# jangeles.net
KiCad netlist of a schematic drawn in EAGLE
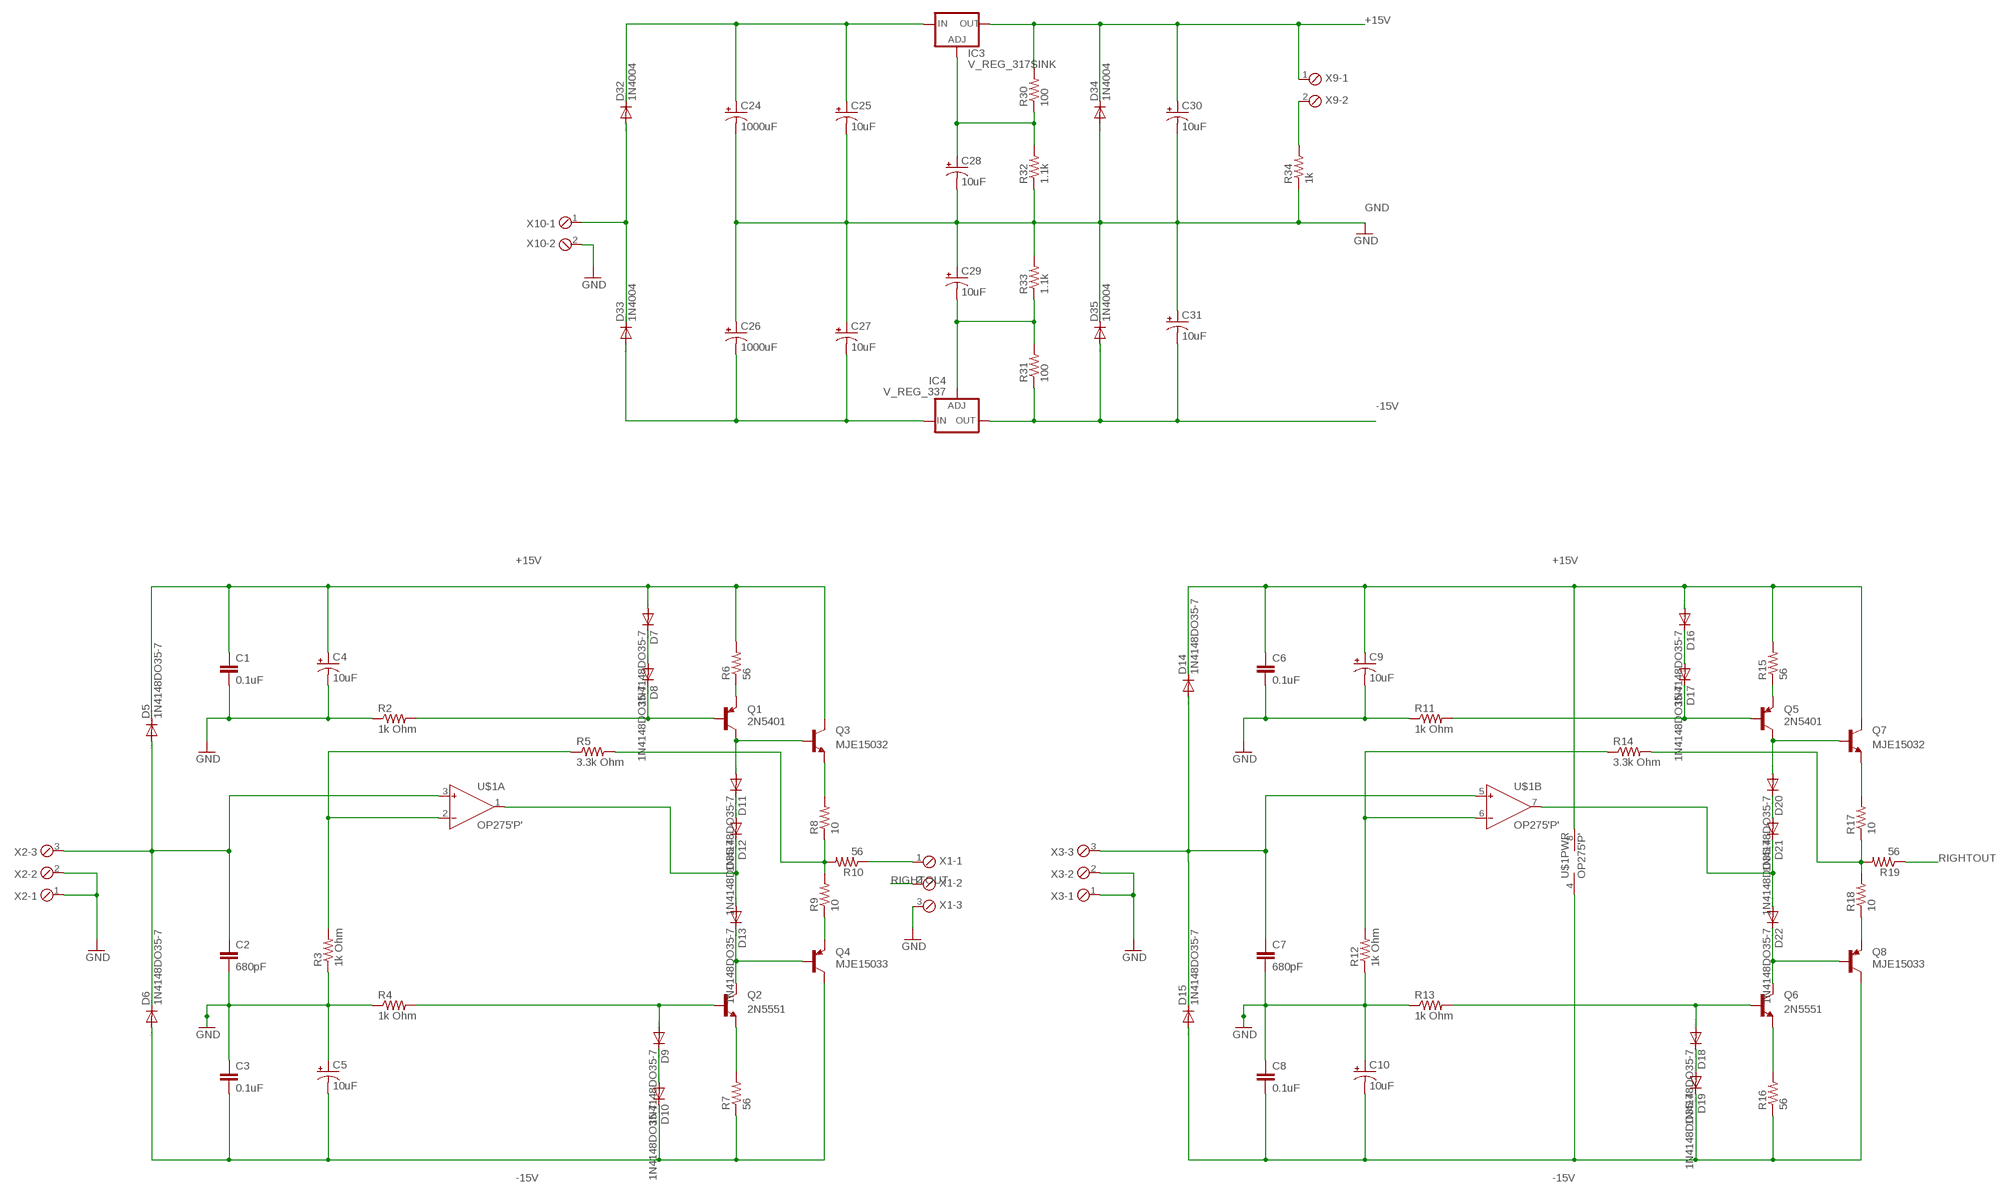
[diagram p0: schematic, sheet 1]

(export (version "E")
  (design (tool "Eeschema 10.0.6"))
  (components
    (comp (ref "C1")
      (value "0.1uF")
      (footprint "eagle-import:C025-024X044")
      (libsource (lib "eagle-import") (part "C-EU025-024X044"))
    )
    (comp (ref "C2")
      (value "680pF")
      (footprint "eagle-import:C025-024X044")
      (libsource (lib "eagle-import") (part "C-EU025-024X044"))
    )
    (comp (ref "C3")
      (value "0.1uF")
      (footprint "eagle-import:C025-024X044")
      (libsource (lib "eagle-import") (part "C-EU025-024X044"))
    )
    (comp (ref "C4")
      (value "10uF")
      (footprint "eagle-import:E2-5")
      (libsource (lib "eagle-import") (part "CPOL-USE2-5"))
    )
    (comp (ref "C5")
      (value "10uF")
      (footprint "eagle-import:E2-5")
      (libsource (lib "eagle-import") (part "CPOL-USE2-5"))
    )
    (comp (ref "C6")
      (value "0.1uF")
      (footprint "eagle-import:C025-024X044")
      (libsource (lib "eagle-import") (part "C-EU025-024X044"))
    )
    (comp (ref "C7")
      (value "680pF")
      (footprint "eagle-import:C025-024X044")
      (libsource (lib "eagle-import") (part "C-EU025-024X044"))
    )
    (comp (ref "C8")
      (value "0.1uF")
      (footprint "eagle-import:C025-024X044")
      (libsource (lib "eagle-import") (part "C-EU025-024X044"))
    )
    (comp (ref "C9")
      (value "10uF")
      (footprint "eagle-import:E2-5")
      (libsource (lib "eagle-import") (part "CPOL-USE2-5"))
    )
    (comp (ref "C10")
      (value "10uF")
      (footprint "eagle-import:E2-5")
      (libsource (lib "eagle-import") (part "CPOL-USE2-5"))
    )
    (comp (ref "C24")
      (value "1000uF")
      (footprint "eagle-import:E5-10,5")
      (libsource (lib "eagle-import") (part "CPOL-USE5-10.5"))
    )
    (comp (ref "C25")
      (value "10uF")
      (footprint "eagle-import:E2-5")
      (libsource (lib "eagle-import") (part "CPOL-USE2-5"))
    )
    (comp (ref "C26")
      (value "1000uF")
      (footprint "eagle-import:E5-10,5")
      (libsource (lib "eagle-import") (part "CPOL-USE5-10.5"))
    )
    (comp (ref "C27")
      (value "10uF")
      (footprint "eagle-import:E2-5")
      (libsource (lib "eagle-import") (part "CPOL-USE2-5"))
    )
    (comp (ref "C28")
      (value "10uF")
      (footprint "eagle-import:E2-5")
      (libsource (lib "eagle-import") (part "CPOL-USE2-5"))
    )
    (comp (ref "C29")
      (value "10uF")
      (footprint "eagle-import:E2-5")
      (libsource (lib "eagle-import") (part "CPOL-USE2-5"))
    )
    (comp (ref "C30")
      (value "10uF")
      (footprint "eagle-import:E2-5")
      (libsource (lib "eagle-import") (part "CPOL-USE2-5"))
    )
    (comp (ref "C31")
      (value "10uF")
      (footprint "eagle-import:E2-5")
      (libsource (lib "eagle-import") (part "CPOL-USE2-5"))
    )
    (comp (ref "D5")
      (value "1N4148DO35-7")
      (footprint "eagle-import:DO35-7")
      (libsource (lib "eagle-import") (part "1N4148DO35-7"))
    )
    (comp (ref "D6")
      (value "1N4148DO35-7")
      (footprint "eagle-import:DO35-7")
      (libsource (lib "eagle-import") (part "1N4148DO35-7"))
    )
    (comp (ref "D7")
      (value "1N4148DO35-7")
      (footprint "eagle-import:DO35-7")
      (libsource (lib "eagle-import") (part "1N4148DO35-7"))
    )
    (comp (ref "D8")
      (value "1N4148DO35-7")
      (footprint "eagle-import:DO35-7")
      (libsource (lib "eagle-import") (part "1N4148DO35-7"))
    )
    (comp (ref "D9")
      (value "1N4148DO35-7")
      (footprint "eagle-import:DO35-7")
      (libsource (lib "eagle-import") (part "1N4148DO35-7"))
    )
    (comp (ref "D10")
      (value "1N4148DO35-7")
      (footprint "eagle-import:DO35-7")
      (libsource (lib "eagle-import") (part "1N4148DO35-7"))
    )
    (comp (ref "D11")
      (value "1N4148DO35-7")
      (footprint "eagle-import:DO35-7")
      (libsource (lib "eagle-import") (part "1N4148DO35-7"))
    )
    (comp (ref "D12")
      (value "1N4148DO35-7")
      (footprint "eagle-import:DO35-7")
      (libsource (lib "eagle-import") (part "1N4148DO35-7"))
    )
    (comp (ref "D13")
      (value "1N4148DO35-7")
      (footprint "eagle-import:DO35-7")
      (libsource (lib "eagle-import") (part "1N4148DO35-7"))
    )
    (comp (ref "D14")
      (value "1N4148DO35-7")
      (footprint "eagle-import:DO35-7")
      (libsource (lib "eagle-import") (part "1N4148DO35-7"))
    )
    (comp (ref "D15")
      (value "1N4148DO35-7")
      (footprint "eagle-import:DO35-7")
      (libsource (lib "eagle-import") (part "1N4148DO35-7"))
    )
    (comp (ref "D16")
      (value "1N4148DO35-7")
      (footprint "eagle-import:DO35-7")
      (libsource (lib "eagle-import") (part "1N4148DO35-7"))
    )
    (comp (ref "D17")
      (value "1N4148DO35-7")
      (footprint "eagle-import:DO35-7")
      (libsource (lib "eagle-import") (part "1N4148DO35-7"))
    )
    (comp (ref "D18")
      (value "1N4148DO35-7")
      (footprint "eagle-import:DO35-7")
      (libsource (lib "eagle-import") (part "1N4148DO35-7"))
    )
    (comp (ref "D19")
      (value "1N4148DO35-7")
      (footprint "eagle-import:DO35-7")
      (libsource (lib "eagle-import") (part "1N4148DO35-7"))
    )
    (comp (ref "D20")
      (value "1N4148DO35-7")
      (footprint "eagle-import:DO35-7")
      (libsource (lib "eagle-import") (part "1N4148DO35-7"))
    )
    (comp (ref "D21")
      (value "1N4148DO35-7")
      (footprint "eagle-import:DO35-7")
      (libsource (lib "eagle-import") (part "1N4148DO35-7"))
    )
    (comp (ref "D22")
      (value "1N4148DO35-7")
      (footprint "eagle-import:DO35-7")
      (libsource (lib "eagle-import") (part "1N4148DO35-7"))
    )
    (comp (ref "D32")
      (value "1N4004")
      (footprint "eagle-import:DO41-10")
      (libsource (lib "eagle-import") (part "1N4004"))
    )
    (comp (ref "D33")
      (value "1N4004")
      (footprint "eagle-import:DO41-10")
      (libsource (lib "eagle-import") (part "1N4004"))
    )
    (comp (ref "D34")
      (value "1N4004")
      (footprint "eagle-import:DO41-10")
      (libsource (lib "eagle-import") (part "1N4004"))
    )
    (comp (ref "D35")
      (value "1N4004")
      (footprint "eagle-import:DO41-10")
      (libsource (lib "eagle-import") (part "1N4004"))
    )
    (comp (ref "IC3")
      (value "V_REG_317SINK")
      (footprint "eagle-import:TO220-ADJ")
      (libsource (lib "eagle-import") (part "V_REG_317SINK"))
    )
    (comp (ref "IC4")
      (value "V_REG_337")
      (footprint "eagle-import:TO220-ADJ-NEG")
      (libsource (lib "eagle-import") (part "V_REG_337"))
    )
    (comp (ref "Q1")
      (value "2N5401")
      (footprint "eagle-import:2N5401")
      (libsource (lib "eagle-import") (part "2N5401"))
    )
    (comp (ref "Q2")
      (value "2N5551")
      (footprint "eagle-import:2N5551")
      (libsource (lib "eagle-import") (part "2N5551"))
    )
    (comp (ref "Q3")
      (value "MJE15032")
      (footprint "eagle-import:TO220V")
      (libsource (lib "eagle-import") (part "MJE15032"))
    )
    (comp (ref "Q4")
      (value "MJE15033")
      (footprint "eagle-import:TO220V")
      (libsource (lib "eagle-import") (part "MJE15033"))
    )
    (comp (ref "Q5")
      (value "2N5401")
      (footprint "eagle-import:2N5401")
      (libsource (lib "eagle-import") (part "2N5401"))
    )
    (comp (ref "Q6")
      (value "2N5551")
      (footprint "eagle-import:2N5551")
      (libsource (lib "eagle-import") (part "2N5551"))
    )
    (comp (ref "Q7")
      (value "MJE15032")
      (footprint "eagle-import:TO220V")
      (libsource (lib "eagle-import") (part "MJE15032"))
    )
    (comp (ref "Q8")
      (value "MJE15033")
      (footprint "eagle-import:TO220V")
      (libsource (lib "eagle-import") (part "MJE15033"))
    )
    (comp (ref "R2")
      (value "1k Ohm")
      (footprint "eagle-import:0204_5")
      (libsource (lib "eagle-import") (part "R-US_0204/5"))
    )
    (comp (ref "R3")
      (value "1k Ohm")
      (footprint "eagle-import:0204_5")
      (libsource (lib "eagle-import") (part "R-US_0204/5"))
    )
    (comp (ref "R4")
      (value "1k Ohm")
      (footprint "eagle-import:0204_5")
      (libsource (lib "eagle-import") (part "R-US_0204/5"))
    )
    (comp (ref "R5")
      (value "3.3k Ohm")
      (footprint "eagle-import:0204_5")
      (libsource (lib "eagle-import") (part "R-US_0204/5"))
    )
    (comp (ref "R6")
      (value "56")
      (footprint "eagle-import:0204_5")
      (libsource (lib "eagle-import") (part "R-US_0204/5"))
    )
    (comp (ref "R7")
      (value "56")
      (footprint "eagle-import:0204_5")
      (libsource (lib "eagle-import") (part "R-US_0204/5"))
    )
    (comp (ref "R8")
      (value "10")
      (footprint "eagle-import:0204_5")
      (libsource (lib "eagle-import") (part "R-US_0204/5"))
    )
    (comp (ref "R9")
      (value "10")
      (footprint "eagle-import:0204_5")
      (libsource (lib "eagle-import") (part "R-US_0204/5"))
    )
    (comp (ref "R10")
      (value "56")
      (footprint "eagle-import:0204_5")
      (libsource (lib "eagle-import") (part "R-US_0204/5"))
    )
    (comp (ref "R11")
      (value "1k Ohm")
      (footprint "eagle-import:0204_5")
      (libsource (lib "eagle-import") (part "R-US_0204/5"))
    )
    (comp (ref "R12")
      (value "1k Ohm")
      (footprint "eagle-import:0204_5")
      (libsource (lib "eagle-import") (part "R-US_0204/5"))
    )
    (comp (ref "R13")
      (value "1k Ohm")
      (footprint "eagle-import:0204_5")
      (libsource (lib "eagle-import") (part "R-US_0204/5"))
    )
    (comp (ref "R14")
      (value "3.3k Ohm")
      (footprint "eagle-import:0204_5")
      (libsource (lib "eagle-import") (part "R-US_0204/5"))
    )
    (comp (ref "R15")
      (value "56")
      (footprint "eagle-import:0204_5")
      (libsource (lib "eagle-import") (part "R-US_0204/5"))
    )
    (comp (ref "R16")
      (value "56")
      (footprint "eagle-import:0204_5")
      (libsource (lib "eagle-import") (part "R-US_0204/5"))
    )
    (comp (ref "R17")
      (value "10")
      (footprint "eagle-import:0204_5")
      (libsource (lib "eagle-import") (part "R-US_0204/5"))
    )
    (comp (ref "R18")
      (value "10")
      (footprint "eagle-import:0204_5")
      (libsource (lib "eagle-import") (part "R-US_0204/5"))
    )
    (comp (ref "R19")
      (value "56")
      (footprint "eagle-import:0204_5")
      (libsource (lib "eagle-import") (part "R-US_0204/5"))
    )
    (comp (ref "R30")
      (value "100")
      (footprint "eagle-import:0309_10")
      (libsource (lib "eagle-import") (part "R-US_0309/10"))
    )
    (comp (ref "R31")
      (value "100")
      (footprint "eagle-import:0309_10")
      (libsource (lib "eagle-import") (part "R-US_0309/10"))
    )
    (comp (ref "R32")
      (value "1.1k")
      (footprint "eagle-import:0204_5")
      (libsource (lib "eagle-import") (part "R-US_0204/5"))
    )
    (comp (ref "R33")
      (value "1.1k")
      (footprint "eagle-import:0204_5")
      (libsource (lib "eagle-import") (part "R-US_0204/5"))
    )
    (comp (ref "R34")
      (value "1k")
      (footprint "eagle-import:0204_5")
      (libsource (lib "eagle-import") (part "R-US_0204/5"))
    )
    (comp (ref "U$1")
      (value "OP275'P'")
      (footprint "eagle-import:DIL08")
      (libsource (lib "eagle-import") (part "OP275'P'"))
    )
    (comp (ref "X1")
      (value "MPT3")
      (footprint "eagle-import:3POL254")
      (libsource (lib "eagle-import") (part "MPT3"))
    )
    (comp (ref "X2")
      (value "MPT3")
      (footprint "eagle-import:3POL254")
      (libsource (lib "eagle-import") (part "MPT3"))
    )
    (comp (ref "X3")
      (value "MPT3")
      (footprint "eagle-import:3POL254")
      (libsource (lib "eagle-import") (part "MPT3"))
    )
    (comp (ref "X9")
      (value "MPT2")
      (footprint "eagle-import:2POL254")
      (libsource (lib "eagle-import") (part "MPT2"))
    )
    (comp (ref "X10")
      (value "MPT2")
      (footprint "eagle-import:2POL254")
      (libsource (lib "eagle-import") (part "MPT2"))
    )
  )
  (nets
    (net (code "1") (name "/+15V") (class "Default")
      (node (ref "C1") (pin "1") (pinfunction "1_1") (pintype "passive"))
      (node (ref "C30") (pin "+") (pinfunction "+_+") (pintype "passive"))
      (node (ref "C4") (pin "+") (pinfunction "+_+") (pintype "passive"))
      (node (ref "C6") (pin "1") (pinfunction "1_1") (pintype "passive"))
      (node (ref "C9") (pin "+") (pinfunction "+_+") (pintype "passive"))
      (node (ref "D14") (pin "C") (pinfunction "C_C") (pintype "passive"))
      (node (ref "D16") (pin "A") (pinfunction "A_A") (pintype "passive"))
      (node (ref "D34") (pin "C") (pinfunction "C_C") (pintype "passive"))
      (node (ref "D5") (pin "C") (pinfunction "C_C") (pintype "passive"))
      (node (ref "D7") (pin "A") (pinfunction "A_A") (pintype "passive"))
      (node (ref "IC3") (pin "OUT") (pinfunction "OUT_OUT") (pintype "output"))
      (node (ref "Q3") (pin "2") (pinfunction "C_2") (pintype "passive"))
      (node (ref "Q7") (pin "2") (pinfunction "C_2") (pintype "passive"))
      (node (ref "R15") (pin "2") (pinfunction "2_2") (pintype "passive"))
      (node (ref "R30") (pin "2") (pinfunction "2_2") (pintype "passive"))
      (node (ref "R6") (pin "2") (pinfunction "2_2") (pintype "passive"))
      (node (ref "U$1") (pin "8") (pinfunction "V+_8") (pintype "power_in"))
      (node (ref "X9") (pin "1") (pinfunction "1_1") (pintype "passive"))
    )
    (net (code "2") (name "/-15V") (class "Default")
      (node (ref "C10") (pin "-") (pinfunction "-_-") (pintype "passive"))
      (node (ref "C3") (pin "2") (pinfunction "2_2") (pintype "passive"))
      (node (ref "C31") (pin "-") (pinfunction "-_-") (pintype "passive"))
      (node (ref "C5") (pin "-") (pinfunction "-_-") (pintype "passive"))
      (node (ref "C8") (pin "2") (pinfunction "2_2") (pintype "passive"))
      (node (ref "D10") (pin "C") (pinfunction "C_C") (pintype "passive"))
      (node (ref "D15") (pin "A") (pinfunction "A_A") (pintype "passive"))
      (node (ref "D19") (pin "C") (pinfunction "C_C") (pintype "passive"))
      (node (ref "D35") (pin "A") (pinfunction "A_A") (pintype "passive"))
      (node (ref "D6") (pin "A") (pinfunction "A_A") (pintype "passive"))
      (node (ref "IC4") (pin "OUT") (pinfunction "OUT_OUT") (pintype "output"))
      (node (ref "Q4") (pin "2") (pinfunction "C_2") (pintype "passive"))
      (node (ref "Q8") (pin "2") (pinfunction "C_2") (pintype "passive"))
      (node (ref "R16") (pin "1") (pinfunction "1_1") (pintype "passive"))
      (node (ref "R31") (pin "1") (pinfunction "1_1") (pintype "passive"))
      (node (ref "R7") (pin "1") (pinfunction "1_1") (pintype "passive"))
      (node (ref "U$1") (pin "4") (pinfunction "V-_4") (pintype "power_in"))
    )
    (net (code "3") (name "/RIGHTOUT") (class "Default")
      (node (ref "R19") (pin "1") (pinfunction "1_1") (pintype "passive"))
      (node (ref "X1") (pin "2") (pinfunction "1_2") (pintype "passive"))
    )
    (net (code "4") (name "GND") (class "Default")
      (node (ref "C1") (pin "2") (pinfunction "2_2") (pintype "passive"))
      (node (ref "C10") (pin "+") (pinfunction "+_+") (pintype "passive"))
      (node (ref "C2") (pin "2") (pinfunction "2_2") (pintype "passive"))
      (node (ref "C24") (pin "-") (pinfunction "-_-") (pintype "passive"))
      (node (ref "C25") (pin "-") (pinfunction "-_-") (pintype "passive"))
      (node (ref "C26") (pin "+") (pinfunction "+_+") (pintype "passive"))
      (node (ref "C27") (pin "+") (pinfunction "+_+") (pintype "passive"))
      (node (ref "C28") (pin "-") (pinfunction "-_-") (pintype "passive"))
      (node (ref "C29") (pin "+") (pinfunction "+_+") (pintype "passive"))
      (node (ref "C3") (pin "1") (pinfunction "1_1") (pintype "passive"))
      (node (ref "C30") (pin "-") (pinfunction "-_-") (pintype "passive"))
      (node (ref "C31") (pin "+") (pinfunction "+_+") (pintype "passive"))
      (node (ref "C4") (pin "-") (pinfunction "-_-") (pintype "passive"))
      (node (ref "C5") (pin "+") (pinfunction "+_+") (pintype "passive"))
      (node (ref "C6") (pin "2") (pinfunction "2_2") (pintype "passive"))
      (node (ref "C7") (pin "2") (pinfunction "2_2") (pintype "passive"))
      (node (ref "C8") (pin "1") (pinfunction "1_1") (pintype "passive"))
      (node (ref "C9") (pin "-") (pinfunction "-_-") (pintype "passive"))
      (node (ref "D34") (pin "A") (pinfunction "A_A") (pintype "passive"))
      (node (ref "D35") (pin "C") (pinfunction "C_C") (pintype "passive"))
      (node (ref "R11") (pin "1") (pinfunction "1_1") (pintype "passive"))
      (node (ref "R12") (pin "1") (pinfunction "1_1") (pintype "passive"))
      (node (ref "R13") (pin "1") (pinfunction "1_1") (pintype "passive"))
      (node (ref "R2") (pin "1") (pinfunction "1_1") (pintype "passive"))
      (node (ref "R3") (pin "1") (pinfunction "1_1") (pintype "passive"))
      (node (ref "R32") (pin "1") (pinfunction "1_1") (pintype "passive"))
      (node (ref "R33") (pin "2") (pinfunction "2_2") (pintype "passive"))
      (node (ref "R34") (pin "1") (pinfunction "1_1") (pintype "passive"))
      (node (ref "R4") (pin "1") (pinfunction "1_1") (pintype "passive"))
      (node (ref "X1") (pin "3") (pinfunction "1_3") (pintype "passive"))
      (node (ref "X10") (pin "2") (pinfunction "1_2") (pintype "passive"))
      (node (ref "X2") (pin "1") (pinfunction "1_1") (pintype "passive"))
      (node (ref "X2") (pin "2") (pinfunction "1_2") (pintype "passive"))
      (node (ref "X3") (pin "1") (pinfunction "1_1") (pintype "passive"))
      (node (ref "X3") (pin "2") (pinfunction "1_2") (pintype "passive"))
    )
    (net (code "5") (name "Net-(C24-Pad+)") (class "Default")
      (node (ref "C24") (pin "+") (pinfunction "+_+") (pintype "passive"))
      (node (ref "C25") (pin "+") (pinfunction "+_+") (pintype "passive"))
      (node (ref "D32") (pin "C") (pinfunction "C_C") (pintype "passive"))
      (node (ref "IC3") (pin "IN") (pinfunction "IN_IN") (pintype "input"))
    )
    (net (code "6") (name "Net-(C26-Pad-)") (class "Default")
      (node (ref "C26") (pin "-") (pinfunction "-_-") (pintype "passive"))
      (node (ref "C27") (pin "-") (pinfunction "-_-") (pintype "passive"))
      (node (ref "D33") (pin "A") (pinfunction "A_A") (pintype "passive"))
      (node (ref "IC4") (pin "IN") (pinfunction "IN_IN") (pintype "input"))
    )
    (net (code "7") (name "Net-(C28-Pad+)") (class "Default")
      (node (ref "C28") (pin "+") (pinfunction "+_+") (pintype "passive"))
      (node (ref "IC3") (pin "ADJ") (pinfunction "ADJ_ADJ") (pintype "input"))
      (node (ref "R30") (pin "1") (pinfunction "1_1") (pintype "passive"))
      (node (ref "R32") (pin "2") (pinfunction "2_2") (pintype "passive"))
    )
    (net (code "8") (name "Net-(C29-Pad-)") (class "Default")
      (node (ref "C29") (pin "-") (pinfunction "-_-") (pintype "passive"))
      (node (ref "IC4") (pin "ADJ") (pinfunction "ADJ_ADJ") (pintype "input"))
      (node (ref "R31") (pin "2") (pinfunction "2_2") (pintype "passive"))
      (node (ref "R33") (pin "1") (pinfunction "1_1") (pintype "passive"))
    )
    (net (code "9") (name "Net-(D7-PadC)") (class "Default")
      (node (ref "D7") (pin "C") (pinfunction "C_C") (pintype "passive"))
      (node (ref "D8") (pin "A") (pinfunction "A_A") (pintype "passive"))
    )
    (net (code "10") (name "Net-(D8-PadC)") (class "Default")
      (node (ref "D8") (pin "C") (pinfunction "C_C") (pintype "passive"))
      (node (ref "Q1") (pin "B") (pinfunction "B_B") (pintype "passive"))
      (node (ref "R2") (pin "2") (pinfunction "2_2") (pintype "passive"))
    )
    (net (code "11") (name "Net-(D9-PadA)") (class "Default")
      (node (ref "D9") (pin "A") (pinfunction "A_A") (pintype "passive"))
      (node (ref "Q2") (pin "B") (pinfunction "B_B") (pintype "passive"))
      (node (ref "R4") (pin "2") (pinfunction "2_2") (pintype "passive"))
    )
    (net (code "12") (name "Net-(D10-PadA)") (class "Default")
      (node (ref "D10") (pin "A") (pinfunction "A_A") (pintype "passive"))
      (node (ref "D9") (pin "C") (pinfunction "C_C") (pintype "passive"))
    )
    (net (code "13") (name "Net-(D11-PadC)") (class "Default")
      (node (ref "D11") (pin "C") (pinfunction "C_C") (pintype "passive"))
      (node (ref "D12") (pin "A") (pinfunction "A_A") (pintype "passive"))
    )
    (net (code "14") (name "Net-(D16-PadC)") (class "Default")
      (node (ref "D16") (pin "C") (pinfunction "C_C") (pintype "passive"))
      (node (ref "D17") (pin "A") (pinfunction "A_A") (pintype "passive"))
    )
    (net (code "15") (name "Net-(D17-PadC)") (class "Default")
      (node (ref "D17") (pin "C") (pinfunction "C_C") (pintype "passive"))
      (node (ref "Q5") (pin "B") (pinfunction "B_B") (pintype "passive"))
      (node (ref "R11") (pin "2") (pinfunction "2_2") (pintype "passive"))
    )
    (net (code "16") (name "Net-(D18-PadA)") (class "Default")
      (node (ref "D18") (pin "A") (pinfunction "A_A") (pintype "passive"))
      (node (ref "Q6") (pin "B") (pinfunction "B_B") (pintype "passive"))
      (node (ref "R13") (pin "2") (pinfunction "2_2") (pintype "passive"))
    )
    (net (code "17") (name "Net-(D18-PadC)") (class "Default")
      (node (ref "D18") (pin "C") (pinfunction "C_C") (pintype "passive"))
      (node (ref "D19") (pin "A") (pinfunction "A_A") (pintype "passive"))
    )
    (net (code "18") (name "Net-(D20-PadC)") (class "Default")
      (node (ref "D20") (pin "C") (pinfunction "C_C") (pintype "passive"))
      (node (ref "D21") (pin "A") (pinfunction "A_A") (pintype "passive"))
    )
    (net (code "19") (name "Net-(D32-PadA)") (class "Default")
      (node (ref "D32") (pin "A") (pinfunction "A_A") (pintype "passive"))
      (node (ref "D33") (pin "C") (pinfunction "C_C") (pintype "passive"))
      (node (ref "X10") (pin "1") (pinfunction "1_1") (pintype "passive"))
    )
    (net (code "20") (name "Net-(Q1-PadE)") (class "Default")
      (node (ref "Q1") (pin "E") (pinfunction "E_E") (pintype "passive"))
      (node (ref "R6") (pin "1") (pinfunction "1_1") (pintype "passive"))
    )
    (net (code "21") (name "Net-(Q2-PadE)") (class "Default")
      (node (ref "Q2") (pin "E") (pinfunction "E_E") (pintype "passive"))
      (node (ref "R7") (pin "2") (pinfunction "2_2") (pintype "passive"))
    )
    (net (code "22") (name "Net-(Q3-B)") (class "Default")
      (node (ref "D11") (pin "A") (pinfunction "A_A") (pintype "passive"))
      (node (ref "Q1") (pin "C") (pinfunction "C_C") (pintype "passive"))
      (node (ref "Q3") (pin "1") (pinfunction "B_1") (pintype "passive"))
    )
    (net (code "23") (name "Net-(Q3-E)") (class "Default")
      (node (ref "Q3") (pin "3") (pinfunction "E_3") (pintype "passive"))
      (node (ref "R8") (pin "2") (pinfunction "2_2") (pintype "passive"))
    )
    (net (code "24") (name "Net-(Q4-B)") (class "Default")
      (node (ref "D13") (pin "C") (pinfunction "C_C") (pintype "passive"))
      (node (ref "Q2") (pin "C") (pinfunction "C_C") (pintype "passive"))
      (node (ref "Q4") (pin "1") (pinfunction "B_1") (pintype "passive"))
    )
    (net (code "25") (name "Net-(Q4-E)") (class "Default")
      (node (ref "Q4") (pin "3") (pinfunction "E_3") (pintype "passive"))
      (node (ref "R9") (pin "1") (pinfunction "1_1") (pintype "passive"))
    )
    (net (code "26") (name "Net-(Q5-PadE)") (class "Default")
      (node (ref "Q5") (pin "E") (pinfunction "E_E") (pintype "passive"))
      (node (ref "R15") (pin "1") (pinfunction "1_1") (pintype "passive"))
    )
    (net (code "27") (name "Net-(Q6-PadE)") (class "Default")
      (node (ref "Q6") (pin "E") (pinfunction "E_E") (pintype "passive"))
      (node (ref "R16") (pin "2") (pinfunction "2_2") (pintype "passive"))
    )
    (net (code "28") (name "Net-(Q7-B)") (class "Default")
      (node (ref "D20") (pin "A") (pinfunction "A_A") (pintype "passive"))
      (node (ref "Q5") (pin "C") (pinfunction "C_C") (pintype "passive"))
      (node (ref "Q7") (pin "1") (pinfunction "B_1") (pintype "passive"))
    )
    (net (code "29") (name "Net-(Q7-E)") (class "Default")
      (node (ref "Q7") (pin "3") (pinfunction "E_3") (pintype "passive"))
      (node (ref "R17") (pin "2") (pinfunction "2_2") (pintype "passive"))
    )
    (net (code "30") (name "Net-(Q8-B)") (class "Default")
      (node (ref "D22") (pin "C") (pinfunction "C_C") (pintype "passive"))
      (node (ref "Q6") (pin "C") (pinfunction "C_C") (pintype "passive"))
      (node (ref "Q8") (pin "1") (pinfunction "B_1") (pintype "passive"))
    )
    (net (code "31") (name "Net-(Q8-E)") (class "Default")
      (node (ref "Q8") (pin "3") (pinfunction "E_3") (pintype "passive"))
      (node (ref "R18") (pin "1") (pinfunction "1_1") (pintype "passive"))
    )
    (net (code "32") (name "Net-(R10-Pad1)") (class "Default")
      (node (ref "R10") (pin "1") (pinfunction "1_1") (pintype "passive"))
      (node (ref "X1") (pin "1") (pinfunction "1_1") (pintype "passive"))
    )
    (net (code "33") (name "Net-(R10-Pad2)") (class "Default")
      (node (ref "R10") (pin "2") (pinfunction "2_2") (pintype "passive"))
      (node (ref "R5") (pin "2") (pinfunction "2_2") (pintype "passive"))
      (node (ref "R8") (pin "1") (pinfunction "1_1") (pintype "passive"))
      (node (ref "R9") (pin "2") (pinfunction "2_2") (pintype "passive"))
    )
    (net (code "34") (name "Net-(R14-Pad2)") (class "Default")
      (node (ref "R14") (pin "2") (pinfunction "2_2") (pintype "passive"))
      (node (ref "R17") (pin "1") (pinfunction "1_1") (pintype "passive"))
      (node (ref "R18") (pin "2") (pinfunction "2_2") (pintype "passive"))
      (node (ref "R19") (pin "2") (pinfunction "2_2") (pintype "passive"))
    )
    (net (code "35") (name "Net-(U$1A-IN+)") (class "Default")
      (node (ref "C2") (pin "1") (pinfunction "1_1") (pintype "passive"))
      (node (ref "D5") (pin "A") (pinfunction "A_A") (pintype "passive"))
      (node (ref "D6") (pin "C") (pinfunction "C_C") (pintype "passive"))
      (node (ref "U$1") (pin "3") (pinfunction "IN+_3") (pintype "input"))
      (node (ref "X2") (pin "3") (pinfunction "1_3") (pintype "passive"))
    )
    (net (code "36") (name "Net-(U$1A-IN-)") (class "Default")
      (node (ref "R3") (pin "2") (pinfunction "2_2") (pintype "passive"))
      (node (ref "R5") (pin "1") (pinfunction "1_1") (pintype "passive"))
      (node (ref "U$1") (pin "2") (pinfunction "IN-_2") (pintype "input"))
    )
    (net (code "37") (name "Net-(U$1A-OUT)") (class "Default")
      (node (ref "D12") (pin "C") (pinfunction "C_C") (pintype "passive"))
      (node (ref "D13") (pin "A") (pinfunction "A_A") (pintype "passive"))
      (node (ref "U$1") (pin "1") (pinfunction "OUT_1") (pintype "output"))
    )
    (net (code "38") (name "Net-(U$1B-IN+)") (class "Default")
      (node (ref "C7") (pin "1") (pinfunction "1_1") (pintype "passive"))
      (node (ref "D14") (pin "A") (pinfunction "A_A") (pintype "passive"))
      (node (ref "D15") (pin "C") (pinfunction "C_C") (pintype "passive"))
      (node (ref "U$1") (pin "5") (pinfunction "IN+_5") (pintype "input"))
      (node (ref "X3") (pin "3") (pinfunction "1_3") (pintype "passive"))
    )
    (net (code "39") (name "Net-(U$1B-IN-)") (class "Default")
      (node (ref "R12") (pin "2") (pinfunction "2_2") (pintype "passive"))
      (node (ref "R14") (pin "1") (pinfunction "1_1") (pintype "passive"))
      (node (ref "U$1") (pin "6") (pinfunction "IN-_6") (pintype "input"))
    )
    (net (code "40") (name "Net-(U$1B-OUT)") (class "Default")
      (node (ref "D21") (pin "C") (pinfunction "C_C") (pintype "passive"))
      (node (ref "D22") (pin "A") (pinfunction "A_A") (pintype "passive"))
      (node (ref "U$1") (pin "7") (pinfunction "OUT_7") (pintype "output"))
    )
    (net (code "41") (name "Net-(X9B-1)") (class "Default")
      (node (ref "R34") (pin "2") (pinfunction "2_2") (pintype "passive"))
      (node (ref "X9") (pin "2") (pinfunction "1_2") (pintype "passive"))
    )
  )
)
